# Avionicapart1.net
KiCad netlist of a schematic drawn in EAGLE
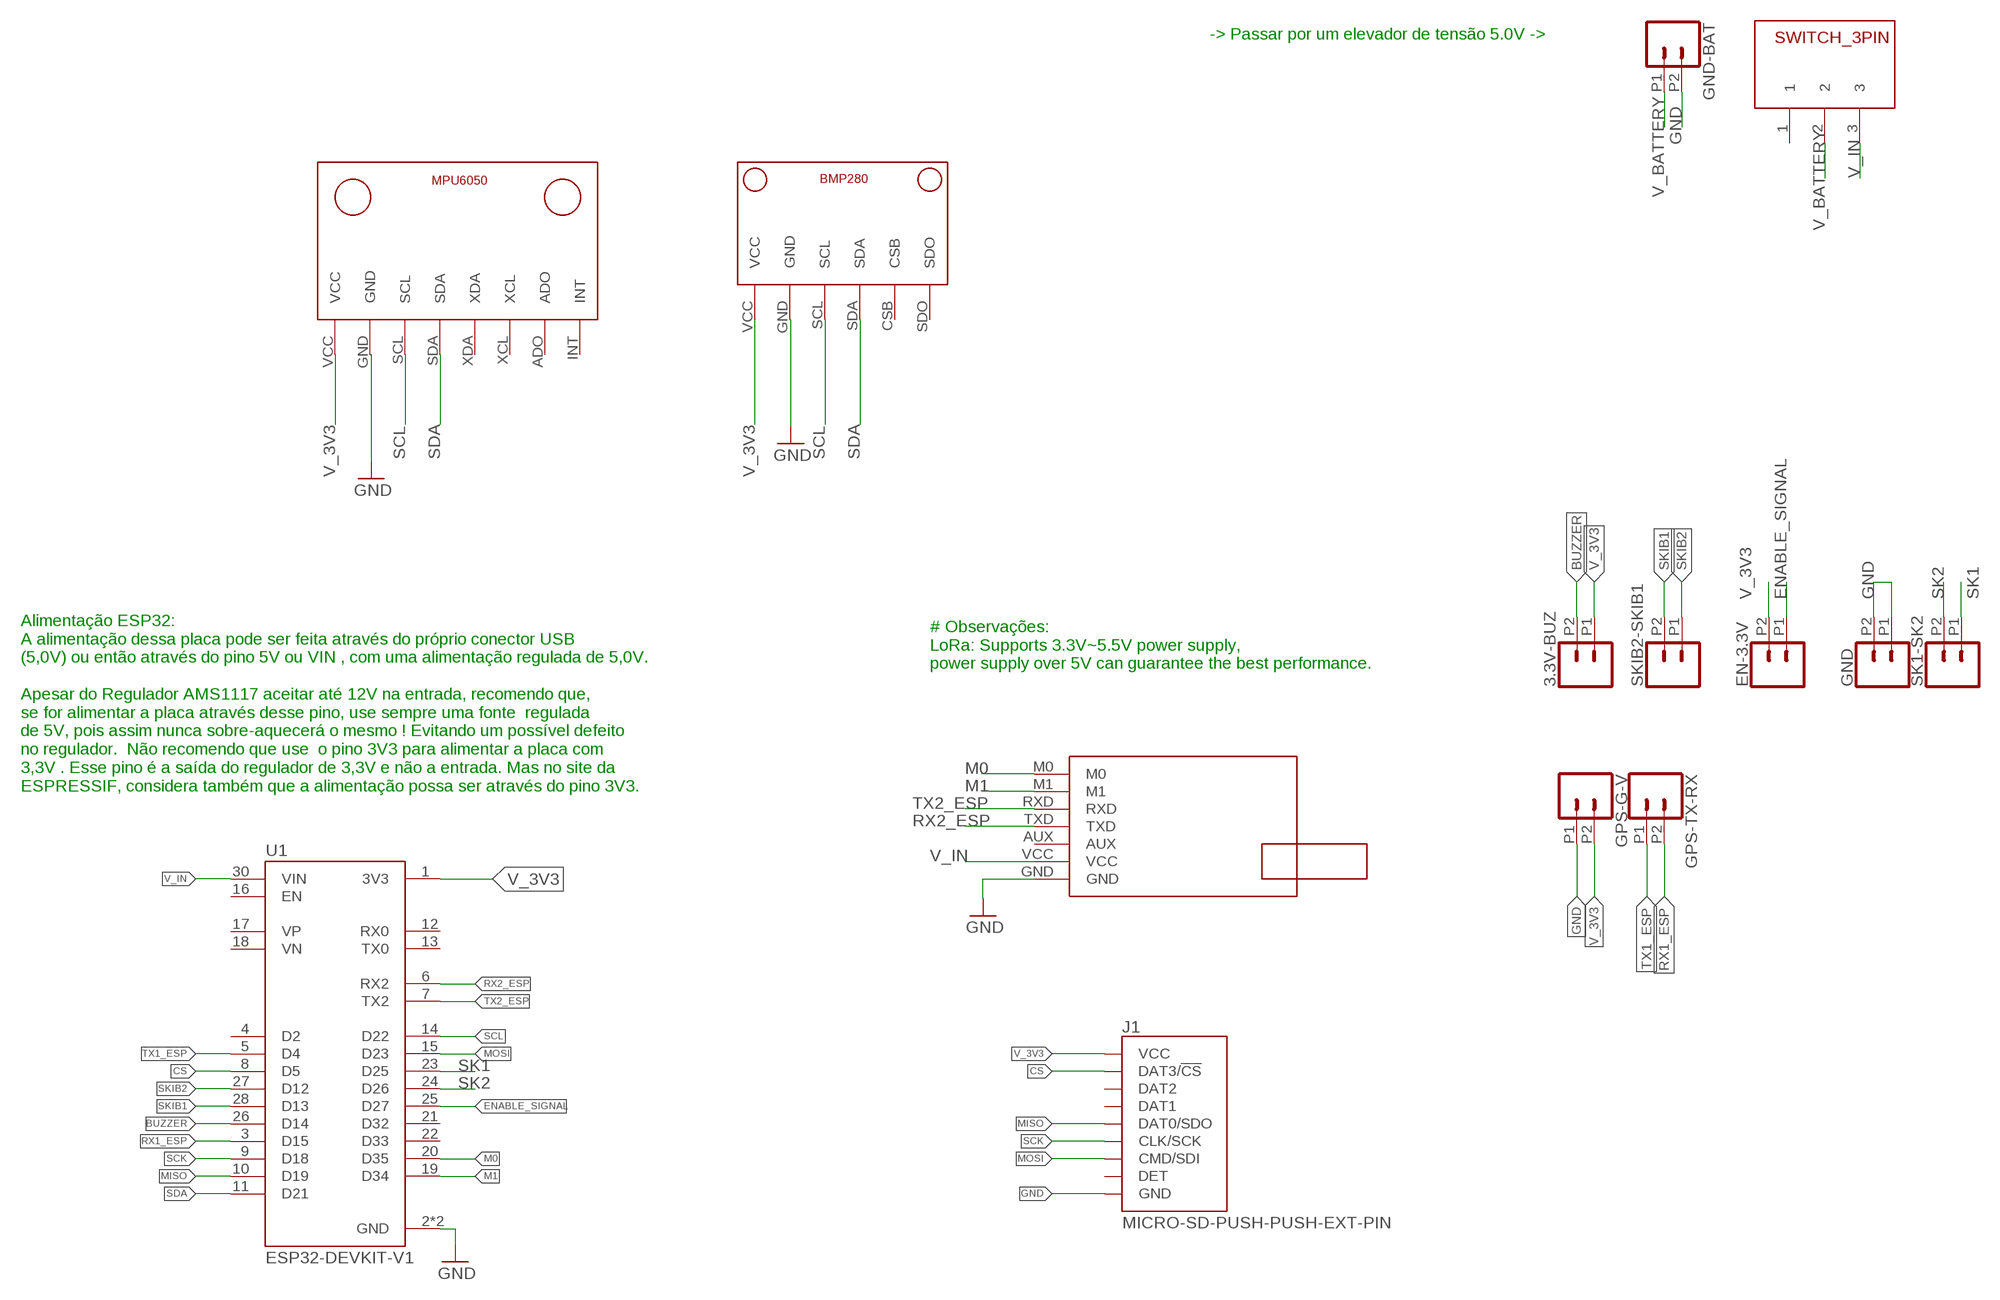
[diagram p0: schematic, sheet 1]

(export (version "E")
  (design (tool "Eeschema 10.0.6"))
  (components
    (comp (ref "3.3V-BUZ")
      (value "CONN_022.54MM_SCREWTERM")
      (footprint "eagle-import:1X02_2.54_SCREWTERM")
      (libsource (lib "eagle-import") (part "CONN_022.54MM_SCREWTERM"))
    )
    (comp (ref "EN-3.3V")
      (value "CONN_022.54MM_SCREWTERM")
      (footprint "eagle-import:1X02_2.54_SCREWTERM")
      (libsource (lib "eagle-import") (part "CONN_022.54MM_SCREWTERM"))
    )
    (comp (ref "GND")
      (value "CONN_022.54MM_SCREWTERM")
      (footprint "eagle-import:1X02_2.54_SCREWTERM")
      (libsource (lib "eagle-import") (part "CONN_022.54MM_SCREWTERM"))
    )
    (comp (ref "GND-BAT")
      (value "CONN_022.54MM_SCREWTERM")
      (footprint "eagle-import:1X02_2.54_SCREWTERM")
      (libsource (lib "eagle-import") (part "CONN_022.54MM_SCREWTERM"))
    )
    (comp (ref "GPS-G-V")
      (value "CONN_022.54MM_SCREWTERM")
      (footprint "eagle-import:1X02_2.54_SCREWTERM")
      (libsource (lib "eagle-import") (part "CONN_022.54MM_SCREWTERM"))
    )
    (comp (ref "GPS-TX-RX")
      (value "CONN_022.54MM_SCREWTERM")
      (footprint "eagle-import:1X02_2.54_SCREWTERM")
      (libsource (lib "eagle-import") (part "CONN_022.54MM_SCREWTERM"))
    )
    (comp (ref "J1")
      (value "MICRO-SD-PUSH-PUSH-EXT-PIN")
      (footprint "eagle-import:MICROSD-EXTERNALPIN")
      (libsource (lib "eagle-import") (part "MICRO-SD-PUSH-PUSH-EXT-PIN"))
    )
    (comp (ref "SK1-SK2")
      (value "CONN_022.54MM_SCREWTERM")
      (footprint "eagle-import:1X02_2.54_SCREWTERM")
      (libsource (lib "eagle-import") (part "CONN_022.54MM_SCREWTERM"))
    )
    (comp (ref "SKIB2-SKIB1")
      (value "CONN_022.54MM_SCREWTERM")
      (footprint "eagle-import:1X02_2.54_SCREWTERM")
      (libsource (lib "eagle-import") (part "CONN_022.54MM_SCREWTERM"))
    )
    (comp (ref "U$2")
      (value "E22-400T30D")
      (footprint "eagle-import:E22-400T30D_FOOTPRINT")
      (libsource (lib "eagle-import") (part "E22-400T30D"))
    )
    (comp (ref "U$4")
      (value "BMP280V1")
      (footprint "eagle-import:BMP280_FOOTPRINT")
      (libsource (lib "eagle-import") (part "BMP280V1"))
    )
    (comp (ref "U$6")
      (value "MPU6050V1")
      (footprint "eagle-import:MPU6050_FOOTPRINT")
      (libsource (lib "eagle-import") (part "MPU6050V1"))
    )
    (comp (ref "U$11")
      (value "SWITCH_3PIN")
      (footprint "eagle-import:SWITCH_3PIN")
      (libsource (lib "eagle-import") (part "SWITCH_3PIN"))
    )
    (comp (ref "U1")
      (value "ESP32-DEVKIT-V1")
      (footprint "eagle-import:MODULE_ESP32_DEVKIT_V1")
      (fields (field (name "MF") "Do it"))
      (libsource (lib "eagle-import") (part "ESP32-DEVKIT-V1"))
    )
  )
  (nets
    (net (code "1") (name "/SK1") (class "Default")
      (node (ref "SK1-SK2") (pin "P1") (pinfunction "1_P1") (pintype "passive"))
      (node (ref "U1") (pin "23") (pinfunction "D25_23") (pintype "bidirectional"))
    )
    (net (code "2") (name "/SK2") (class "Default")
      (node (ref "SK1-SK2") (pin "P2") (pinfunction "2_P2") (pintype "passive"))
      (node (ref "U1") (pin "24") (pinfunction "D26_24") (pintype "bidirectional"))
    )
    (net (code "3") (name "/V_BATTERY") (class "Default")
      (node (ref "GND-BAT") (pin "P1") (pinfunction "1_P1") (pintype "passive"))
      (node (ref "U$11") (pin "2") (pinfunction "2_2") (pintype "bidirectional"))
    )
    (net (code "4") (name "BUZZER") (class "Default")
      (node (ref "3.3V-BUZ") (pin "P2") (pinfunction "2_P2") (pintype "passive"))
      (node (ref "U1") (pin "26") (pinfunction "D14_26") (pintype "bidirectional"))
    )
    (net (code "5") (name "CS") (class "Default")
      (node (ref "J1") (pin "2") (pinfunction "DAT3/~{CS}_2") (pintype "bidirectional"))
      (node (ref "U1") (pin "8") (pinfunction "D5_8") (pintype "bidirectional"))
    )
    (net (code "6") (name "ENABLE_SIGNAL") (class "Default")
      (node (ref "EN-3.3V") (pin "P1") (pinfunction "1_P1") (pintype "passive"))
      (node (ref "U1") (pin "25") (pinfunction "D27_25") (pintype "bidirectional"))
    )
    (net (code "7") (name "GND") (class "Default")
      (node (ref "GND") (pin "P1") (pinfunction "1_P1") (pintype "passive"))
      (node (ref "GND") (pin "P2") (pinfunction "2_P2") (pintype "passive"))
      (node (ref "GND-BAT") (pin "P2") (pinfunction "2_P2") (pintype "passive"))
      (node (ref "GPS-G-V") (pin "P1") (pinfunction "1_P1") (pintype "passive"))
      (node (ref "J1") (pin "10") (pinfunction "GND_10") (pintype "bidirectional"))
      (node (ref "J1") (pin "11") (pinfunction "GND_11") (pintype "bidirectional"))
      (node (ref "J1") (pin "12") (pinfunction "GND_12") (pintype "bidirectional"))
      (node (ref "J1") (pin "13") (pinfunction "GND_13") (pintype "bidirectional"))
      (node (ref "J1") (pin "6") (pinfunction "GND_6") (pintype "bidirectional"))
      (node (ref "U$2") (pin "GND") (pinfunction "GND_GND") (pintype "bidirectional"))
      (node (ref "U$4") (pin "GND") (pinfunction "GND_GND") (pintype "bidirectional"))
      (node (ref "U$6") (pin "GND") (pinfunction "GND_GND") (pintype "bidirectional"))
      (node (ref "U1") (pin "2") (pinfunction "GND_2") (pintype "power_in"))
      (node (ref "U1") (pin "29") (pinfunction "GND_29") (pintype "power_in"))
    )
    (net (code "8") (name "M0") (class "Default")
      (node (ref "U$2") (pin "M0") (pinfunction "M0_M0") (pintype "bidirectional"))
      (node (ref "U1") (pin "20") (pinfunction "D35_20") (pintype "bidirectional"))
    )
    (net (code "9") (name "M1") (class "Default")
      (node (ref "U$2") (pin "M1") (pinfunction "M1_M1") (pintype "bidirectional"))
      (node (ref "U1") (pin "19") (pinfunction "D34_19") (pintype "bidirectional"))
    )
    (net (code "10") (name "MISO") (class "Default")
      (node (ref "J1") (pin "7") (pinfunction "DAT0/SDO_7") (pintype "bidirectional"))
      (node (ref "U1") (pin "10") (pinfunction "D19_10") (pintype "bidirectional"))
    )
    (net (code "11") (name "MOSI") (class "Default")
      (node (ref "J1") (pin "3") (pinfunction "CMD/SDI_3") (pintype "bidirectional"))
      (node (ref "U1") (pin "15") (pinfunction "D23_15") (pintype "bidirectional"))
    )
    (net (code "12") (name "RX1_ESP") (class "Default")
      (node (ref "GPS-TX-RX") (pin "P2") (pinfunction "2_P2") (pintype "passive"))
      (node (ref "U1") (pin "3") (pinfunction "D15_3") (pintype "bidirectional"))
    )
    (net (code "13") (name "RX2_ESP") (class "Default")
      (node (ref "U$2") (pin "TXD") (pinfunction "TXD_TXD") (pintype "bidirectional"))
      (node (ref "U1") (pin "6") (pinfunction "RX2_6") (pintype "input"))
    )
    (net (code "14") (name "SCK") (class "Default")
      (node (ref "J1") (pin "5") (pinfunction "CLK/SCK_5") (pintype "bidirectional"))
      (node (ref "U1") (pin "9") (pinfunction "D18_9") (pintype "bidirectional"))
    )
    (net (code "15") (name "SCL") (class "Default")
      (node (ref "U$4") (pin "SCL") (pinfunction "SCL_SCL") (pintype "bidirectional"))
      (node (ref "U$6") (pin "SCL") (pinfunction "SCL_SCL") (pintype "bidirectional"))
      (node (ref "U1") (pin "14") (pinfunction "D22_14") (pintype "bidirectional"))
    )
    (net (code "16") (name "SDA") (class "Default")
      (node (ref "U$4") (pin "SDA") (pinfunction "SDA_SDA") (pintype "bidirectional"))
      (node (ref "U$6") (pin "SDA") (pinfunction "SDA_SDA") (pintype "bidirectional"))
      (node (ref "U1") (pin "11") (pinfunction "D21_11") (pintype "bidirectional"))
    )
    (net (code "17") (name "SKIB1") (class "Default")
      (node (ref "SKIB2-SKIB1") (pin "P2") (pinfunction "2_P2") (pintype "passive"))
      (node (ref "U1") (pin "28") (pinfunction "D13_28") (pintype "bidirectional"))
    )
    (net (code "18") (name "SKIB2") (class "Default")
      (node (ref "SKIB2-SKIB1") (pin "P1") (pinfunction "1_P1") (pintype "passive"))
      (node (ref "U1") (pin "27") (pinfunction "D12_27") (pintype "bidirectional"))
    )
    (net (code "19") (name "TX1_ESP") (class "Default")
      (node (ref "GPS-TX-RX") (pin "P1") (pinfunction "1_P1") (pintype "passive"))
      (node (ref "U1") (pin "5") (pinfunction "D4_5") (pintype "bidirectional"))
    )
    (net (code "20") (name "TX2_ESP") (class "Default")
      (node (ref "U$2") (pin "RXD") (pinfunction "RXD_RXD") (pintype "bidirectional"))
      (node (ref "U1") (pin "7") (pinfunction "TX2_7") (pintype "output"))
    )
    (net (code "21") (name "V_3V3") (class "Default")
      (node (ref "3.3V-BUZ") (pin "P1") (pinfunction "1_P1") (pintype "passive"))
      (node (ref "EN-3.3V") (pin "P2") (pinfunction "2_P2") (pintype "passive"))
      (node (ref "GPS-G-V") (pin "P2") (pinfunction "2_P2") (pintype "passive"))
      (node (ref "J1") (pin "4") (pinfunction "VCC_4") (pintype "bidirectional"))
      (node (ref "U$4") (pin "VCC") (pinfunction "VCC_VCC") (pintype "bidirectional"))
      (node (ref "U$6") (pin "VCC") (pinfunction "VCC_VCC") (pintype "bidirectional"))
      (node (ref "U1") (pin "1") (pinfunction "3V3_1") (pintype "output"))
    )
    (net (code "22") (name "V_IN") (class "Default")
      (node (ref "U$11") (pin "3") (pinfunction "3_3") (pintype "bidirectional"))
      (node (ref "U$2") (pin "VCC") (pinfunction "VCC_VCC") (pintype "bidirectional"))
      (node (ref "U1") (pin "30") (pinfunction "VIN_30") (pintype "input"))
    )
    (net (code "23") (name "unconnected-(J1-DAT1-Pad8)") (class "Default")
      (node (ref "J1") (pin "8") (pinfunction "DAT1_8") (pintype "bidirectional"))
    )
    (net (code "24") (name "unconnected-(J1-DAT2-Pad1)") (class "Default")
      (node (ref "J1") (pin "1") (pinfunction "DAT2_1") (pintype "bidirectional"))
    )
    (net (code "25") (name "unconnected-(J1-DET-Pad9)") (class "Default")
      (node (ref "J1") (pin "9") (pinfunction "DET_9") (pintype "bidirectional"))
    )
    (net (code "26") (name "unconnected-(U$2-PadAUX)") (class "Default")
      (node (ref "U$2") (pin "AUX") (pinfunction "AUX_AUX") (pintype "bidirectional"))
    )
    (net (code "27") (name "unconnected-(U$4-PadCSB)") (class "Default")
      (node (ref "U$4") (pin "CSB") (pinfunction "CSB_CSB") (pintype "bidirectional"))
    )
    (net (code "28") (name "unconnected-(U$4-PadSDO)") (class "Default")
      (node (ref "U$4") (pin "SDO") (pinfunction "SDO_SDO") (pintype "bidirectional"))
    )
    (net (code "29") (name "unconnected-(U$6-PadADO)") (class "Default")
      (node (ref "U$6") (pin "ADO") (pinfunction "ADO_ADO") (pintype "bidirectional"))
    )
    (net (code "30") (name "unconnected-(U$6-PadINT)") (class "Default")
      (node (ref "U$6") (pin "INT") (pinfunction "INT_INT") (pintype "bidirectional"))
    )
    (net (code "31") (name "unconnected-(U$6-PadXCL)") (class "Default")
      (node (ref "U$6") (pin "XCL") (pinfunction "XCL_XCL") (pintype "bidirectional"))
    )
    (net (code "32") (name "unconnected-(U$6-PadXDA)") (class "Default")
      (node (ref "U$6") (pin "XDA") (pinfunction "XDA_XDA") (pintype "bidirectional"))
    )
    (net (code "33") (name "unconnected-(U$11-Pad1)") (class "Default")
      (node (ref "U$11") (pin "1") (pinfunction "1_1") (pintype "bidirectional"))
    )
    (net (code "34") (name "unconnected-(U1-D2-Pad4)") (class "Default")
      (node (ref "U1") (pin "4") (pinfunction "D2_4") (pintype "bidirectional"))
    )
    (net (code "35") (name "unconnected-(U1-D32-Pad21)") (class "Default")
      (node (ref "U1") (pin "21") (pinfunction "D32_21") (pintype "bidirectional"))
    )
    (net (code "36") (name "unconnected-(U1-D33-Pad22)") (class "Default")
      (node (ref "U1") (pin "22") (pinfunction "D33_22") (pintype "bidirectional"))
    )
    (net (code "37") (name "unconnected-(U1-EN-Pad16)") (class "Default")
      (node (ref "U1") (pin "16") (pinfunction "EN_16") (pintype "input"))
    )
    (net (code "38") (name "unconnected-(U1-RX0-Pad12)") (class "Default")
      (node (ref "U1") (pin "12") (pinfunction "RX0_12") (pintype "input"))
    )
    (net (code "39") (name "unconnected-(U1-TX0-Pad13)") (class "Default")
      (node (ref "U1") (pin "13") (pinfunction "TX0_13") (pintype "output"))
    )
    (net (code "40") (name "unconnected-(U1-VN-Pad18)") (class "Default")
      (node (ref "U1") (pin "18") (pinfunction "VN_18") (pintype "bidirectional"))
    )
    (net (code "41") (name "unconnected-(U1-VP-Pad17)") (class "Default")
      (node (ref "U1") (pin "17") (pinfunction "VP_17") (pintype "bidirectional"))
    )
  )
)
